# Power.net
KiCad netlist of a schematic drawn in Altium Designer
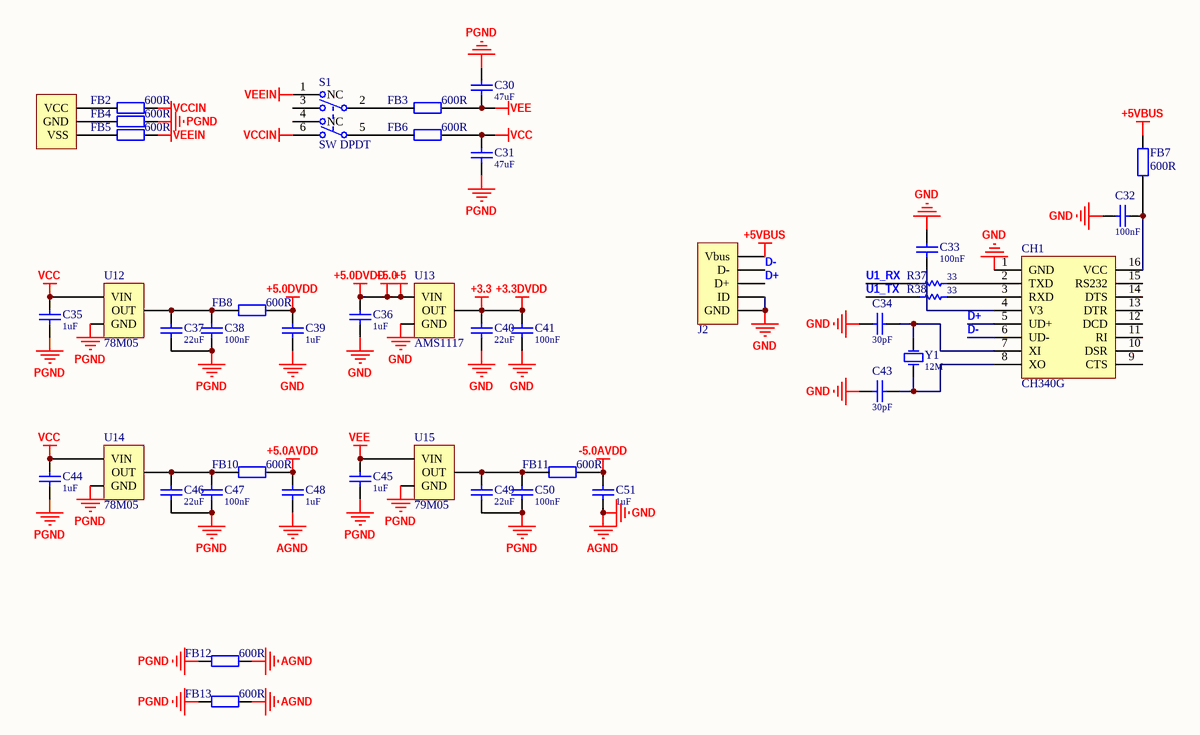
[diagram p0: Power.SchDoc]

(export (version "E")
  (design (tool "Eeschema 10.0.6"))
  (components
    (comp (ref "C30")
      (value "47uF")
      (footprint "C0805-L")
      (description "贴片瓷片电容")
      (fields (field (name "Comment") "Cap-S"))
      (libsource (lib "xz_D") (part "Cap-S"))
    )
    (comp (ref "C31")
      (value "47uF")
      (footprint "C0805-L")
      (description "贴片瓷片电容")
      (fields (field (name "Comment") "Cap-S"))
      (libsource (lib "xz_D") (part "Cap-S"))
    )
    (comp (ref "C32")
      (value "100nF")
      (footprint "C0603-L")
      (description "贴片瓷片电容")
      (fields (field (name "Comment") "Cap-S"))
      (libsource (lib "xz_D") (part "Cap-S"))
    )
    (comp (ref "C33")
      (value "100nF")
      (footprint "C0603-L")
      (description "贴片瓷片电容")
      (fields (field (name "Comment") "Cap-S"))
      (libsource (lib "xz_D") (part "Cap-S"))
    )
    (comp (ref "C34")
      (value "30pF")
      (footprint "C0603-L")
      (description "贴片瓷片电容")
      (fields (field (name "Comment") "Cap-S"))
      (libsource (lib "xz_D") (part "Cap-S"))
    )
    (comp (ref "C35")
      (value "1uF")
      (footprint "C0603-L")
      (description "贴片瓷片电容")
      (fields (field (name "Comment") "Cap-S"))
      (libsource (lib "xz_D") (part "Cap-S"))
    )
    (comp (ref "C36")
      (value "1uF")
      (footprint "C0603-L")
      (description "贴片瓷片电容")
      (fields (field (name "Comment") "Cap-S"))
      (libsource (lib "xz_D") (part "Cap-S"))
    )
    (comp (ref "C37")
      (value "22uF")
      (footprint "C0805-L")
      (description "贴片瓷片电容")
      (fields (field (name "Comment") "Cap-S"))
      (libsource (lib "xz_D") (part "Cap-S"))
    )
    (comp (ref "C38")
      (value "100nF")
      (footprint "C0603-L")
      (description "贴片瓷片电容")
      (fields (field (name "Comment") "Cap-S"))
      (libsource (lib "xz_D") (part "Cap-S"))
    )
    (comp (ref "C39")
      (value "1uF")
      (footprint "C0603-L")
      (description "贴片瓷片电容")
      (fields (field (name "Comment") "Cap-S"))
      (libsource (lib "xz_D") (part "Cap-S"))
    )
    (comp (ref "C40")
      (value "22uF")
      (footprint "C0805-L")
      (description "贴片瓷片电容")
      (fields (field (name "Comment") "Cap-S"))
      (libsource (lib "xz_D") (part "Cap-S"))
    )
    (comp (ref "C41")
      (value "100nF")
      (footprint "C0603-L")
      (description "贴片瓷片电容")
      (fields (field (name "Comment") "Cap-S"))
      (libsource (lib "xz_D") (part "Cap-S"))
    )
    (comp (ref "C43")
      (value "30pF")
      (footprint "C0603-L")
      (description "贴片瓷片电容")
      (fields (field (name "Comment") "Cap-S"))
      (libsource (lib "xz_D") (part "Cap-S"))
    )
    (comp (ref "C44")
      (value "1uF")
      (footprint "C0603-L")
      (description "贴片瓷片电容")
      (fields (field (name "Comment") "Cap-S"))
      (libsource (lib "xz_D") (part "Cap-S"))
    )
    (comp (ref "C45")
      (value "1uF")
      (footprint "C0603-L")
      (description "贴片瓷片电容")
      (fields (field (name "Comment") "Cap-S"))
      (libsource (lib "xz_D") (part "Cap-S"))
    )
    (comp (ref "C46")
      (value "22uF")
      (footprint "C0805-L")
      (description "贴片瓷片电容")
      (fields (field (name "Comment") "Cap-S"))
      (libsource (lib "xz_D") (part "Cap-S"))
    )
    (comp (ref "C47")
      (value "100nF")
      (footprint "C0603-L")
      (description "贴片瓷片电容")
      (fields (field (name "Comment") "Cap-S"))
      (libsource (lib "xz_D") (part "Cap-S"))
    )
    (comp (ref "C48")
      (value "1uF")
      (footprint "C0603-L")
      (description "贴片瓷片电容")
      (fields (field (name "Comment") "Cap-S"))
      (libsource (lib "xz_D") (part "Cap-S"))
    )
    (comp (ref "C49")
      (value "22uF")
      (footprint "C0805-L")
      (description "贴片瓷片电容")
      (fields (field (name "Comment") "Cap-S"))
      (libsource (lib "xz_D") (part "Cap-S"))
    )
    (comp (ref "C50")
      (value "100nF")
      (footprint "C0603-L")
      (description "贴片瓷片电容")
      (fields (field (name "Comment") "Cap-S"))
      (libsource (lib "xz_D") (part "Cap-S"))
    )
    (comp (ref "C51")
      (value "1uF")
      (footprint "C0603-L")
      (description "贴片瓷片电容")
      (fields (field (name "Comment") "Cap-S"))
      (libsource (lib "xz_D") (part "Cap-S"))
    )
    (comp (ref "CH1")
      (value "CH340G")
      (footprint "SOP-16")
      (description "SOP16")
      (libsource (lib "xz_D") (part "CH340G"))
    )
    (comp (ref "FB2") (value "600R") (footprint "FB-0805") (libsource (lib "CommonUsed") (part "FB")))
    (comp (ref "FB3") (value "600R") (footprint "FB-0805") (libsource (lib "CommonUsed") (part "FB")))
    (comp (ref "FB4") (value "600R") (footprint "FB-0805") (libsource (lib "CommonUsed") (part "FB")))
    (comp (ref "FB5") (value "600R") (footprint "FB-0805") (libsource (lib "CommonUsed") (part "FB")))
    (comp (ref "FB6") (value "600R") (footprint "FB-0805") (libsource (lib "CommonUsed") (part "FB")))
    (comp (ref "FB7") (value "600R") (footprint "FB-0805") (libsource (lib "CommonUsed") (part "FB")))
    (comp (ref "FB8") (value "600R") (footprint "FB-0805") (libsource (lib "CommonUsed") (part "FB")))
    (comp (ref "FB10") (value "600R") (footprint "FB-0805") (libsource (lib "CommonUsed") (part "FB")))
    (comp (ref "FB11") (value "600R") (footprint "FB-0805") (libsource (lib "CommonUsed") (part "FB")))
    (comp (ref "FB12") (value "600R") (footprint "FB-0805") (libsource (lib "CommonUsed") (part "FB")))
    (comp (ref "FB13") (value "600R") (footprint "FB-0805") (libsource (lib "CommonUsed") (part "FB")))
    (comp (ref "J1")
      (value "Power-3P")
      (footprint "SIPA03")
      (description "供电端子")
      (libsource (lib "xz_C") (part "Power-3P"))
    )
    (comp (ref "J2")
      (value "USB_Mini/Micro")
      (footprint "USB_MINI_B-L")
      (description "Mini/Micro USB母口")
      (libsource (lib "xz_C") (part "USB"))
    )
    (comp (ref "R37")
      (value "33")
      (footprint "R0603-L")
      (description "贴片电阻")
      (fields (field (name "Comment") "R"))
      (libsource (lib "xz_D") (part "Res"))
    )
    (comp (ref "R38")
      (value "33")
      (footprint "R0603-L")
      (description "贴片电阻")
      (fields (field (name "Comment") "R"))
      (libsource (lib "xz_D") (part "Res"))
    )
    (comp (ref "S1")
      (value "SW DPDT")
      (footprint "SW_DPDT")
      (description "自锁开关")
      (fields (field (name "PUBLISHER") "Altium Limited"))
      (libsource (lib "xz_D") (part "SW DPDT"))
    )
    (comp (ref "U12") (value "78M05") (footprint "TO-252") (libsource (lib "PowerUnits") (part "78M05")))
    (comp (ref "U13") (value "AMS1117") (footprint "SOT-223") (libsource (lib "CommonUsed") (part "AMS1117")))
    (comp (ref "U14") (value "78M05") (footprint "TO-252") (libsource (lib "PowerUnits") (part "78M05")))
    (comp (ref "U15") (value "79M05") (footprint "TO-252") (libsource (lib "PowerUnits") (part "79M05")))
    (comp (ref "Y1")
      (value "12M")
      (footprint "XTAL-PB2-SMD")
      (description "晶振")
      (fields (field (name "Comment") "XTAL"))
      (libsource (lib "xz_D") (part "XTAL"))
    )
  )
  (nets
    (net (code "1") (name "+3.3") (class "Default")
      (node (ref "C40") (pin "2") (pinfunction "2_2") (pintype "passive"))
      (node (ref "C41") (pin "2") (pinfunction "2_2") (pintype "passive"))
      (node (ref "U13") (pin "2") (pinfunction "OUT_2") (pintype "passive"))
    )
    (net (code "2") (name "+5") (class "Default")
      (node (ref "C36") (pin "2") (pinfunction "2_2") (pintype "passive"))
      (node (ref "C39") (pin "2") (pinfunction "2_2") (pintype "passive"))
      (node (ref "FB8") (pin "2") (pinfunction "2_2") (pintype "passive"))
      (node (ref "U13") (pin "3") (pinfunction "VIN_3") (pintype "passive"))
    )
    (net (code "3") (name "+5.0AVDD") (class "Default")
      (node (ref "C48") (pin "2") (pinfunction "2_2") (pintype "passive"))
      (node (ref "FB10") (pin "2") (pinfunction "2_2") (pintype "passive"))
    )
    (net (code "4") (name "+5VBUS") (class "Default")
      (node (ref "FB7") (pin "2") (pinfunction "2_2") (pintype "passive"))
      (node (ref "J2") (pin "1") (pinfunction "Vbus_1") (pintype "passive"))
    )
    (net (code "5") (name "-5.0AVDD") (class "Default")
      (node (ref "C51") (pin "2") (pinfunction "2_2") (pintype "passive"))
      (node (ref "FB11") (pin "2") (pinfunction "2_2") (pintype "passive"))
    )
    (net (code "6") (name "/D+") (class "Default")
      (node (ref "CH1") (pin "5") (pinfunction "UD+_5") (pintype "passive"))
      (node (ref "J2") (pin "3") (pinfunction "D+_3") (pintype "passive"))
    )
    (net (code "7") (name "/D-") (class "Default")
      (node (ref "CH1") (pin "6") (pinfunction "UD-_6") (pintype "passive"))
      (node (ref "J2") (pin "2") (pinfunction "D-_2") (pintype "passive"))
    )
    (net (code "8") (name "/U1_RX") (class "Default")
      (node (ref "R37") (pin "1") (pinfunction "1_1") (pintype "passive"))
    )
    (net (code "9") (name "/U1_TX") (class "Default")
      (node (ref "R38") (pin "1") (pinfunction "1_1") (pintype "passive"))
    )
    (net (code "10") (name "AGND") (class "Default")
      (node (ref "C32") (pin "1") (pinfunction "1_1") (pintype "passive"))
      (node (ref "C33") (pin "1") (pinfunction "1_1") (pintype "passive"))
      (node (ref "C34") (pin "1") (pinfunction "1_1") (pintype "passive"))
      (node (ref "C36") (pin "1") (pinfunction "1_1") (pintype "passive"))
      (node (ref "C39") (pin "1") (pinfunction "1_1") (pintype "passive"))
      (node (ref "C40") (pin "1") (pinfunction "1_1") (pintype "passive"))
      (node (ref "C41") (pin "1") (pinfunction "1_1") (pintype "passive"))
      (node (ref "C43") (pin "1") (pinfunction "1_1") (pintype "passive"))
      (node (ref "C48") (pin "1") (pinfunction "1_1") (pintype "passive"))
      (node (ref "C51") (pin "1") (pinfunction "1_1") (pintype "passive"))
      (node (ref "CH1") (pin "1") (pinfunction "GND_1") (pintype "passive"))
      (node (ref "FB12") (pin "2") (pinfunction "2_2") (pintype "passive"))
      (node (ref "FB13") (pin "2") (pinfunction "2_2") (pintype "passive"))
      (node (ref "J2") (pin "4") (pinfunction "ID_4") (pintype "passive"))
      (node (ref "J2") (pin "5") (pinfunction "GND_5") (pintype "passive"))
      (node (ref "U13") (pin "1") (pinfunction "GND_1") (pintype "passive"))
    )
    (net (code "11") (name "Net-(CH1-RXD)") (class "Default")
      (node (ref "CH1") (pin "3") (pinfunction "RXD_3") (pintype "passive"))
      (node (ref "R38") (pin "2") (pinfunction "2_2") (pintype "passive"))
    )
    (net (code "12") (name "Net-(CH1-TXD)") (class "Default")
      (node (ref "CH1") (pin "2") (pinfunction "TXD_2") (pintype "passive"))
      (node (ref "R37") (pin "2") (pinfunction "2_2") (pintype "passive"))
    )
    (net (code "13") (name "Net-(CH1-V3)") (class "Default")
      (node (ref "C33") (pin "2") (pinfunction "2_2") (pintype "passive"))
      (node (ref "CH1") (pin "4") (pinfunction "V3_4") (pintype "passive"))
    )
    (net (code "14") (name "Net-(CH1-VCC)") (class "Default")
      (node (ref "C32") (pin "2") (pinfunction "2_2") (pintype "passive"))
      (node (ref "CH1") (pin "16") (pinfunction "VCC_16") (pintype "passive"))
      (node (ref "FB7") (pin "1") (pinfunction "1_1") (pintype "passive"))
    )
    (net (code "15") (name "Net-(CH1-XI)") (class "Default")
      (node (ref "C34") (pin "2") (pinfunction "2_2") (pintype "passive"))
      (node (ref "CH1") (pin "7") (pinfunction "XI_7") (pintype "passive"))
      (node (ref "Y1") (pin "2") (pinfunction "OSC2_2") (pintype "passive"))
    )
    (net (code "16") (name "Net-(CH1-XO)") (class "Default")
      (node (ref "C43") (pin "2") (pinfunction "2_2") (pintype "passive"))
      (node (ref "CH1") (pin "8") (pinfunction "XO_8") (pintype "passive"))
      (node (ref "Y1") (pin "1") (pinfunction "OSC1_1") (pintype "passive"))
    )
    (net (code "17") (name "Net-(J1-GND)") (class "Default")
      (node (ref "FB4") (pin "1") (pinfunction "1_1") (pintype "passive"))
      (node (ref "J1") (pin "2") (pinfunction "GND_2") (pintype "passive"))
    )
    (net (code "18") (name "Net-(J1-VCC)") (class "Default")
      (node (ref "FB2") (pin "1") (pinfunction "1_1") (pintype "passive"))
      (node (ref "J1") (pin "1") (pinfunction "VCC_1") (pintype "passive"))
    )
    (net (code "19") (name "Net-(J1-VSS)") (class "Default")
      (node (ref "FB5") (pin "1") (pinfunction "1_1") (pintype "passive"))
      (node (ref "J1") (pin "3") (pinfunction "VSS_3") (pintype "passive"))
    )
    (net (code "20") (name "Net-(S1-1)") (class "Default")
      (node (ref "FB3") (pin "1") (pinfunction "1_1") (pintype "passive"))
      (node (ref "S1") (pin "2") (pinfunction "1_2") (pintype "passive"))
    )
    (net (code "21") (name "Net-(S1-COMMON2)") (class "Default")
      (node (ref "FB6") (pin "1") (pinfunction "1_1") (pintype "passive"))
      (node (ref "S1") (pin "5") (pinfunction "COMMON2_5") (pintype "passive"))
    )
    (net (code "22") (name "Net-(U12-OUT)") (class "Default")
      (node (ref "C37") (pin "2") (pinfunction "2_2") (pintype "passive"))
      (node (ref "C38") (pin "2") (pinfunction "2_2") (pintype "passive"))
      (node (ref "FB8") (pin "1") (pinfunction "1_1") (pintype "passive"))
      (node (ref "U12") (pin "3") (pinfunction "OUT_3") (pintype "passive"))
    )
    (net (code "23") (name "Net-(U14-OUT)") (class "Default")
      (node (ref "C46") (pin "2") (pinfunction "2_2") (pintype "passive"))
      (node (ref "C47") (pin "2") (pinfunction "2_2") (pintype "passive"))
      (node (ref "FB10") (pin "1") (pinfunction "1_1") (pintype "passive"))
      (node (ref "U14") (pin "3") (pinfunction "OUT_3") (pintype "passive"))
    )
    (net (code "24") (name "Net-(U15-OUT)") (class "Default")
      (node (ref "C49") (pin "2") (pinfunction "2_2") (pintype "passive"))
      (node (ref "C50") (pin "2") (pinfunction "2_2") (pintype "passive"))
      (node (ref "FB11") (pin "1") (pinfunction "1_1") (pintype "passive"))
      (node (ref "U15") (pin "3") (pinfunction "OUT_3") (pintype "passive"))
    )
    (net (code "25") (name "PGND") (class "Default")
      (node (ref "C30") (pin "2") (pinfunction "2_2") (pintype "passive"))
      (node (ref "C31") (pin "2") (pinfunction "2_2") (pintype "passive"))
      (node (ref "C35") (pin "1") (pinfunction "1_1") (pintype "passive"))
      (node (ref "C37") (pin "1") (pinfunction "1_1") (pintype "passive"))
      (node (ref "C38") (pin "1") (pinfunction "1_1") (pintype "passive"))
      (node (ref "C44") (pin "1") (pinfunction "1_1") (pintype "passive"))
      (node (ref "C45") (pin "1") (pinfunction "1_1") (pintype "passive"))
      (node (ref "C46") (pin "1") (pinfunction "1_1") (pintype "passive"))
      (node (ref "C47") (pin "1") (pinfunction "1_1") (pintype "passive"))
      (node (ref "C49") (pin "1") (pinfunction "1_1") (pintype "passive"))
      (node (ref "C50") (pin "1") (pinfunction "1_1") (pintype "passive"))
      (node (ref "FB12") (pin "1") (pinfunction "1_1") (pintype "passive"))
      (node (ref "FB13") (pin "1") (pinfunction "1_1") (pintype "passive"))
      (node (ref "FB4") (pin "2") (pinfunction "2_2") (pintype "passive"))
      (node (ref "U12") (pin "2") (pinfunction "GND_2") (pintype "passive"))
      (node (ref "U14") (pin "2") (pinfunction "GND_2") (pintype "passive"))
      (node (ref "U15") (pin "1") (pinfunction "GND_1") (pintype "passive"))
    )
    (net (code "26") (name "VCC") (class "Default")
      (node (ref "C31") (pin "1") (pinfunction "1_1") (pintype "passive"))
      (node (ref "C35") (pin "2") (pinfunction "2_2") (pintype "passive"))
      (node (ref "C44") (pin "2") (pinfunction "2_2") (pintype "passive"))
      (node (ref "FB6") (pin "2") (pinfunction "2_2") (pintype "passive"))
      (node (ref "U12") (pin "1") (pinfunction "VIN_1") (pintype "passive"))
      (node (ref "U14") (pin "1") (pinfunction "VIN_1") (pintype "passive"))
    )
    (net (code "27") (name "VCCIN") (class "Default")
      (node (ref "FB2") (pin "2") (pinfunction "2_2") (pintype "passive"))
      (node (ref "S1") (pin "6") (pinfunction "NO2_6") (pintype "passive"))
    )
    (net (code "28") (name "VEE") (class "Default")
      (node (ref "C30") (pin "1") (pinfunction "1_1") (pintype "passive"))
      (node (ref "C45") (pin "2") (pinfunction "2_2") (pintype "passive"))
      (node (ref "FB3") (pin "2") (pinfunction "2_2") (pintype "passive"))
      (node (ref "U15") (pin "2") (pinfunction "VIN_2") (pintype "passive"))
    )
    (net (code "29") (name "VEEIN") (class "Default")
      (node (ref "FB5") (pin "2") (pinfunction "2_2") (pintype "passive"))
      (node (ref "S1") (pin "1") (pinfunction "NC_1") (pintype "passive"))
    )
    (net (code "30") (name "unconnected-(CH1-CTS-Pad9)") (class "Default")
      (node (ref "CH1") (pin "9") (pinfunction "CTS_9") (pintype "passive"))
    )
    (net (code "31") (name "unconnected-(CH1-DCD-Pad12)") (class "Default")
      (node (ref "CH1") (pin "12") (pinfunction "DCD_12") (pintype "passive"))
    )
    (net (code "32") (name "unconnected-(CH1-DSR-Pad10)") (class "Default")
      (node (ref "CH1") (pin "10") (pinfunction "DSR_10") (pintype "passive"))
    )
    (net (code "33") (name "unconnected-(CH1-DTR-Pad13)") (class "Default")
      (node (ref "CH1") (pin "13") (pinfunction "DTR_13") (pintype "passive"))
    )
    (net (code "34") (name "unconnected-(CH1-DTS-Pad14)") (class "Default")
      (node (ref "CH1") (pin "14") (pinfunction "DTS_14") (pintype "passive"))
    )
    (net (code "35") (name "unconnected-(CH1-RI-Pad11)") (class "Default")
      (node (ref "CH1") (pin "11") (pinfunction "RI_11") (pintype "passive"))
    )
    (net (code "36") (name "unconnected-(CH1-RS232-Pad15)") (class "Default")
      (node (ref "CH1") (pin "15") (pinfunction "RS232_15") (pintype "passive"))
    )
    (net (code "37") (name "unconnected-(S1-NC-Pad4)") (class "Default")
      (node (ref "S1") (pin "4") (pinfunction "NC_4") (pintype "passive"))
    )
    (net (code "38") (name "unconnected-(S1-NO1-Pad3)") (class "Default")
      (node (ref "S1") (pin "3") (pinfunction "NO1_3") (pintype "passive"))
    )
  )
)
